# base_board7.net
KiCad netlist of a schematic drawn in EAGLE
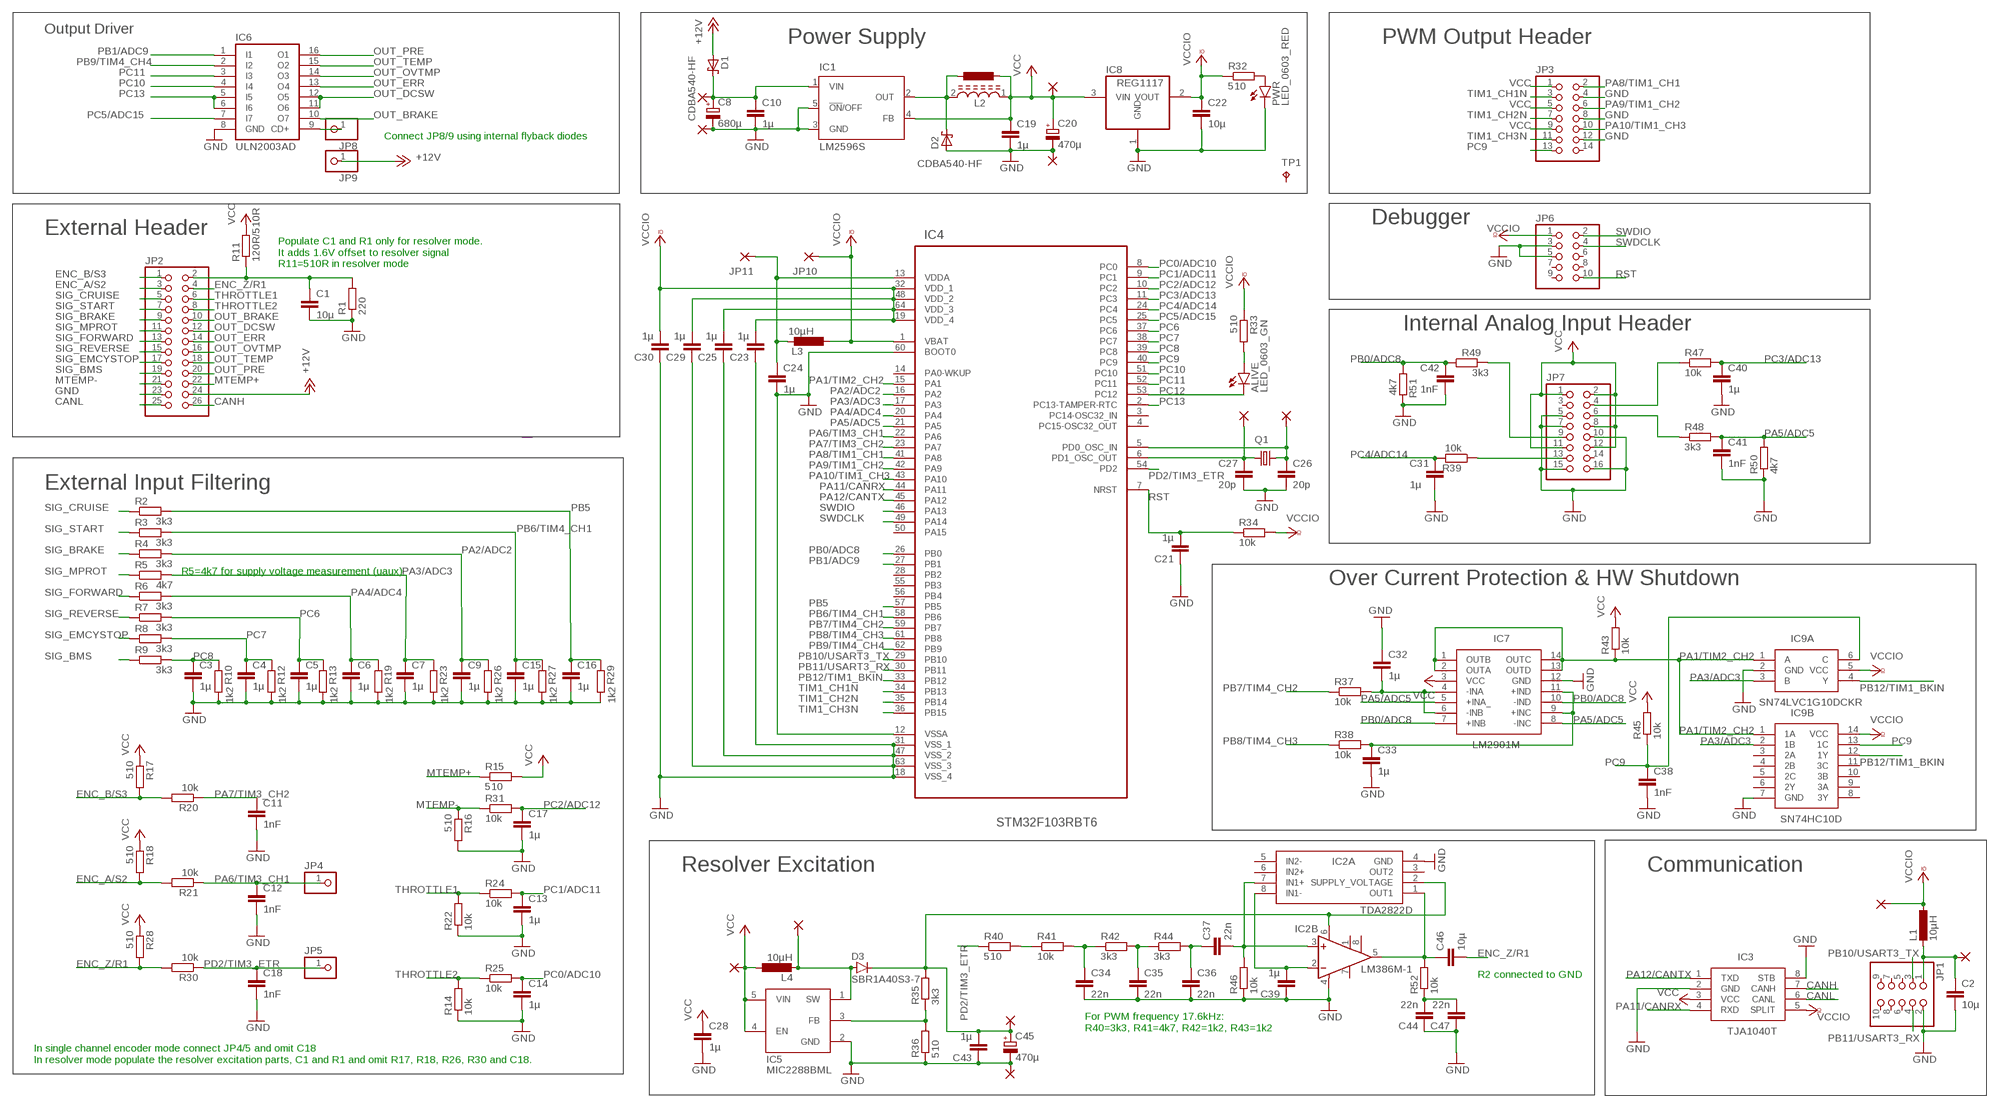
[diagram p0: schematic, sheet 1]

(export (version "E")
  (design (tool "Eeschema 10.0.6"))
  (components
    (comp (ref "ALIVE")
      (value "LED_0603_GN")
      (footprint "eagle-import:SML0805")
      (libsource (lib "eagle-import") (part "LEDSML0805"))
    )
    (comp (ref "C1")
      (value "10µ")
      (footprint "eagle-import:C0805K")
      (libsource (lib "eagle-import") (part "C-EUC0805K"))
    )
    (comp (ref "C2")
      (value "10µ")
      (footprint "eagle-import:C0805K")
      (libsource (lib "eagle-import") (part "C-EUC0805K"))
    )
    (comp (ref "C3")
      (value "1µ")
      (footprint "eagle-import:C0603K")
      (libsource (lib "eagle-import") (part "C-EUC0603K"))
    )
    (comp (ref "C4")
      (value "1µ")
      (footprint "eagle-import:C0603K")
      (libsource (lib "eagle-import") (part "C-EUC0603K"))
    )
    (comp (ref "C5")
      (value "1µ")
      (footprint "eagle-import:C0603K")
      (libsource (lib "eagle-import") (part "C-EUC0603K"))
    )
    (comp (ref "C6")
      (value "1µ")
      (footprint "eagle-import:C0603K")
      (libsource (lib "eagle-import") (part "C-EUC0603K"))
    )
    (comp (ref "C7")
      (value "1µ")
      (footprint "eagle-import:C0603K")
      (libsource (lib "eagle-import") (part "C-EUC0603K"))
    )
    (comp (ref "C8")
      (value "680µ")
      (footprint "eagle-import:153CLV-1014")
      (libsource (lib "eagle-import") (part "CPOL-EU153CLV-1014"))
    )
    (comp (ref "C9")
      (value "1µ")
      (footprint "eagle-import:C0603K")
      (libsource (lib "eagle-import") (part "C-EUC0603K"))
    )
    (comp (ref "C10")
      (value "1µ")
      (footprint "eagle-import:C0603K")
      (libsource (lib "eagle-import") (part "C-EUC0603K"))
    )
    (comp (ref "C11")
      (value "1nF")
      (footprint "eagle-import:C0603K")
      (libsource (lib "eagle-import") (part "C-EUC0603K"))
    )
    (comp (ref "C12")
      (value "1nF")
      (footprint "eagle-import:C0603K")
      (libsource (lib "eagle-import") (part "C-EUC0603K"))
    )
    (comp (ref "C13")
      (value "1µ")
      (footprint "eagle-import:C0603K")
      (libsource (lib "eagle-import") (part "C-EUC0603K"))
    )
    (comp (ref "C14")
      (value "1µ")
      (footprint "eagle-import:C0603K")
      (libsource (lib "eagle-import") (part "C-EUC0603K"))
    )
    (comp (ref "C15")
      (value "1µ")
      (footprint "eagle-import:C0603K")
      (libsource (lib "eagle-import") (part "C-EUC0603K"))
    )
    (comp (ref "C16")
      (value "1µ")
      (footprint "eagle-import:C0603K")
      (libsource (lib "eagle-import") (part "C-EUC0603K"))
    )
    (comp (ref "C17")
      (value "1µ")
      (footprint "eagle-import:C0603K")
      (libsource (lib "eagle-import") (part "C-EUC0603K"))
    )
    (comp (ref "C18")
      (value "1nF")
      (footprint "eagle-import:C0603K")
      (libsource (lib "eagle-import") (part "C-EUC0603K"))
    )
    (comp (ref "C19")
      (value "1µ")
      (footprint "eagle-import:C0603K")
      (libsource (lib "eagle-import") (part "C-EUC0603K"))
    )
    (comp (ref "C20")
      (value "470µ")
      (footprint "eagle-import:153CLV-0605")
      (libsource (lib "eagle-import") (part "CPOL-EU153CLV-0605"))
    )
    (comp (ref "C21")
      (value "1µ")
      (footprint "eagle-import:C0603K")
      (libsource (lib "eagle-import") (part "C-EUC0603K"))
    )
    (comp (ref "C22")
      (value "10µ")
      (footprint "eagle-import:C0805K")
      (libsource (lib "eagle-import") (part "C-EUC0805K"))
    )
    (comp (ref "C23")
      (value "1µ")
      (footprint "eagle-import:C0603K")
      (libsource (lib "eagle-import") (part "C-EUC0603K"))
    )
    (comp (ref "C24")
      (value "1µ")
      (footprint "eagle-import:C0603K")
      (libsource (lib "eagle-import") (part "C-EUC0603K"))
    )
    (comp (ref "C25")
      (value "1µ")
      (footprint "eagle-import:C0603K")
      (libsource (lib "eagle-import") (part "C-EUC0603K"))
    )
    (comp (ref "C26")
      (value "20p")
      (footprint "eagle-import:C0603K")
      (libsource (lib "eagle-import") (part "C-EUC0603K"))
    )
    (comp (ref "C27")
      (value "20p")
      (footprint "eagle-import:C0603K")
      (libsource (lib "eagle-import") (part "C-EUC0603K"))
    )
    (comp (ref "C28")
      (value "1µ")
      (footprint "eagle-import:C0603K")
      (libsource (lib "eagle-import") (part "C-EUC0603K"))
    )
    (comp (ref "C29")
      (value "1µ")
      (footprint "eagle-import:C0603K")
      (libsource (lib "eagle-import") (part "C-EUC0603K"))
    )
    (comp (ref "C30")
      (value "1µ")
      (footprint "eagle-import:C0603K")
      (libsource (lib "eagle-import") (part "C-EUC0603K"))
    )
    (comp (ref "C31")
      (value "1µ")
      (footprint "eagle-import:C0603K")
      (libsource (lib "eagle-import") (part "C-EUC0603K"))
    )
    (comp (ref "C32")
      (value "1µ")
      (footprint "eagle-import:C0603K")
      (libsource (lib "eagle-import") (part "C-EUC0603K"))
    )
    (comp (ref "C33")
      (value "1µ")
      (footprint "eagle-import:C0603K")
      (libsource (lib "eagle-import") (part "C-EUC0603K"))
    )
    (comp (ref "C34")
      (value "22n")
      (footprint "eagle-import:C0603K")
      (libsource (lib "eagle-import") (part "C-EUC0603K"))
    )
    (comp (ref "C35")
      (value "22n")
      (footprint "eagle-import:C0603K")
      (libsource (lib "eagle-import") (part "C-EUC0603K"))
    )
    (comp (ref "C36")
      (value "22n")
      (footprint "eagle-import:C0603K")
      (libsource (lib "eagle-import") (part "C-EUC0603K"))
    )
    (comp (ref "C37")
      (value "22n")
      (footprint "eagle-import:C0603K")
      (libsource (lib "eagle-import") (part "C-EUC0603K"))
    )
    (comp (ref "C38")
      (value "1nF")
      (footprint "eagle-import:C0603K")
      (libsource (lib "eagle-import") (part "C-EUC0603K"))
    )
    (comp (ref "C39")
      (value "1µ")
      (footprint "eagle-import:C0603K")
      (libsource (lib "eagle-import") (part "C-EUC0603K"))
    )
    (comp (ref "C40")
      (value "1µ")
      (footprint "eagle-import:C0603K")
      (libsource (lib "eagle-import") (part "C-EUC0603K"))
    )
    (comp (ref "C41")
      (value "1nF")
      (footprint "eagle-import:C0603K")
      (libsource (lib "eagle-import") (part "C-EUC0603K"))
    )
    (comp (ref "C42")
      (value "1nF")
      (footprint "eagle-import:C0603K")
      (libsource (lib "eagle-import") (part "C-EUC0603K"))
    )
    (comp (ref "C43")
      (value "1µ")
      (footprint "eagle-import:C0603K")
      (libsource (lib "eagle-import") (part "C-EUC0603K"))
    )
    (comp (ref "C44")
      (value "22n")
      (footprint "eagle-import:C0603K")
      (libsource (lib "eagle-import") (part "C-EUC0603K"))
    )
    (comp (ref "C45")
      (value "470µ")
      (footprint "eagle-import:153CLV-0605")
      (libsource (lib "eagle-import") (part "CPOL-EU153CLV-0605"))
    )
    (comp (ref "C46")
      (value "10µ")
      (footprint "eagle-import:C0805K")
      (libsource (lib "eagle-import") (part "C-EUC0805K"))
    )
    (comp (ref "C47")
      (value "22n")
      (footprint "eagle-import:C0603K")
      (libsource (lib "eagle-import") (part "C-EUC0603K"))
    )
    (comp (ref "D1")
      (value "CDBA540-HF")
      (footprint "eagle-import:SMB")
      (libsource (lib "eagle-import") (part "SCHOTTKY-DIODESMD"))
    )
    (comp (ref "D2")
      (value "CDBA540-HF")
      (footprint "eagle-import:SMB")
      (libsource (lib "eagle-import") (part "SCHOTTKY-DIODESMD"))
    )
    (comp (ref "D3")
      (value "SBR1A40S3-7")
      (footprint "eagle-import:SOD123")
      (libsource (lib "eagle-import") (part "D-SOD123"))
    )
    (comp (ref "IC1")
      (value "LM2596S")
      (footprint "eagle-import:TO263-5")
      (fields (field (name "MF") "NATIONAL SEMICONDUCTOR") (field (name "MPN") "LM2596S-ADJ/NOPB"))
      (libsource (lib "eagle-import") (part "LM2596S"))
    )
    (comp (ref "IC2A")
      (value "TDA2822D")
      (footprint "eagle-import:SOIC127P600X175-8N")
      (fields (field (name "MOUSER_PART_NUMBER") "511-TDA2822D") (field (name "RS_PART_NUMBER") "0426162P"))
      (libsource (lib "eagle-import") (part "TDA2822D"))
    )
    (comp (ref "IC2B")
      (value "LM386M-1")
      (footprint "eagle-import:SO08")
      (libsource (lib "eagle-import") (part "LM386?-M1"))
    )
    (comp (ref "IC3")
      (value "TJA1040T")
      (footprint "eagle-import:SOIC127P600X175-8N")
      (fields (field (name "MOUSER_PART_NUMBER") "4837547"))
      (libsource (lib "eagle-import") (part "TJA1040T"))
    )
    (comp (ref "IC4")
      (value "STM32F103RBT6")
      (footprint "eagle-import:QFP50P1200X1200X160-64N")
      (fields (field (name "DIGI-KEY_PART_NUMBER") "497-6066-ND") (field (name "MF") "STMicroelectronics"))
      (libsource (lib "eagle-import") (part "STM32F103RBT6"))
    )
    (comp (ref "IC5")
      (value "MIC2288BML")
      (footprint "eagle-import:SOT23-5L")
      (libsource (lib "eagle-import") (part "MIC2288BML"))
    )
    (comp (ref "IC6")
      (value "ULN2003AD")
      (footprint "eagle-import:SO16")
      (libsource (lib "eagle-import") (part "ULN2003AD"))
    )
    (comp (ref "IC7")
      (value "LM2901M")
      (footprint "eagle-import:SOP127P600X180-14N")
      (fields (field (name "MOUSER_PART_NUMBER") "4716204"))
      (libsource (lib "eagle-import") (part "LM2901M"))
    )
    (comp (ref "IC8")
      (value "REG1117")
      (footprint "eagle-import:SOT223")
      (libsource (lib "eagle-import") (part "REG1117"))
    )
    (comp (ref "IC9A")
      (value "SN74LVC1G10DCKR")
      (footprint "eagle-import:SOT65P210X110-6N")
      (fields
        (field (name "MOUSER_PART_NUMBER") "595-SN74LVC1G10DCKR")
        (field (name "RS_PART_NUMBER") "1627462")
      )
      (libsource (lib "eagle-import") (part "SN74LVC1G10DCKR"))
    )
    (comp (ref "IC9B")
      (value "SN74HC10D")
      (footprint "eagle-import:SOIC127P600X175-14N")
      (fields (field (name "MOUSER_PART_NUMBER") "595-SN74HC10D") (field (name "RS_PART_NUMBER") "6631896P"))
      (libsource (lib "eagle-import") (part "SN74HC10D"))
    )
    (comp (ref "JP1")
      (value "PINHD-2X5/90")
      (footprint "eagle-import:2X05_90")
      (libsource (lib "eagle-import") (part "PINHD-2X5/90"))
    )
    (comp (ref "JP2")
      (value "PINHD-2X13")
      (footprint "eagle-import:2X13")
      (libsource (lib "eagle-import") (part "PINHD-2X13"))
    )
    (comp (ref "JP3")
      (value "PINHD-2X7")
      (footprint "eagle-import:2X07")
      (libsource (lib "eagle-import") (part "PINHD-2X7"))
    )
    (comp (ref "JP4")
      (value "PINHD-1X1")
      (footprint "eagle-import:1X01")
      (libsource (lib "eagle-import") (part "PINHD-1X1"))
    )
    (comp (ref "JP5")
      (value "PINHD-1X1")
      (footprint "eagle-import:1X01")
      (libsource (lib "eagle-import") (part "PINHD-1X1"))
    )
    (comp (ref "JP6")
      (value "PINHD-2X5")
      (footprint "eagle-import:2X05")
      (libsource (lib "eagle-import") (part "PINHD-2X5"))
    )
    (comp (ref "JP7")
      (value "PINHD-2X8")
      (footprint "eagle-import:2X08")
      (libsource (lib "eagle-import") (part "PINHD-2X8"))
    )
    (comp (ref "JP8")
      (value "PINHD-1X1")
      (footprint "eagle-import:1X01")
      (libsource (lib "eagle-import") (part "PINHD-1X1"))
    )
    (comp (ref "JP9")
      (value "PINHD-1X1")
      (footprint "eagle-import:1X01")
      (libsource (lib "eagle-import") (part "PINHD-1X1"))
    )
    (comp (ref "JP10")
      (value "1,6/0,9")
      (footprint "eagle-import:1,6_0,9")
      (libsource (lib "eagle-import") (part "1,6/0,9"))
    )
    (comp (ref "JP11")
      (value "1,6/0,9")
      (footprint "eagle-import:1,6_0,9")
      (libsource (lib "eagle-import") (part "1,6/0,9"))
    )
    (comp (ref "JP12")
      (value "1,6/0,8")
      (footprint "eagle-import:1,6_0,8")
      (libsource (lib "eagle-import") (part "1,6/0,8"))
    )
    (comp (ref "JP13")
      (value "1,6/0,8")
      (footprint "eagle-import:1,6_0,8")
      (libsource (lib "eagle-import") (part "1,6/0,8"))
    )
    (comp (ref "JP14")
      (value "1,6/0,8")
      (footprint "eagle-import:1,6_0,8")
      (libsource (lib "eagle-import") (part "1,6/0,8"))
    )
    (comp (ref "JP15")
      (value "1,6/0,8")
      (footprint "eagle-import:1,6_0,8")
      (libsource (lib "eagle-import") (part "1,6/0,8"))
    )
    (comp (ref "JP16")
      (value "1,6/0,8")
      (footprint "eagle-import:1,6_0,8")
      (libsource (lib "eagle-import") (part "1,6/0,8"))
    )
    (comp (ref "JP17")
      (value "1,6/0,8")
      (footprint "eagle-import:1,6_0,8")
      (libsource (lib "eagle-import") (part "1,6/0,8"))
    )
    (comp (ref "L1")
      (value "10µH")
      (footprint "eagle-import:L3225M")
      (libsource (lib "eagle-import") (part "L-EUL3225M"))
    )
    (comp (ref "L2")
      (value "SRR1260-471K")
      (footprint "eagle-import:INDP125125X600N")
      (fields (field (name "MF") "Bourns"))
      (libsource (lib "eagle-import") (part "SRR1260-471K"))
    )
    (comp (ref "L3")
      (value "10µH")
      (footprint "eagle-import:L3225M")
      (libsource (lib "eagle-import") (part "L-EUL3225M"))
    )
    (comp (ref "L4")
      (value "10µH")
      (footprint "eagle-import:L3225M")
      (libsource (lib "eagle-import") (part "L-EUL3225M"))
    )
    (comp (ref "L5")
      (value "L-EUTJ3-U1")
      (footprint "eagle-import:TJ3-U1")
      (libsource (lib "eagle-import") (part "resistor_348_L-EUTJ3-U1"))
    )
    (comp (ref "PAD1")
      (value "1,6/0,9")
      (footprint "eagle-import:1,6_0,9")
      (libsource (lib "eagle-import") (part "1,6/0,9"))
    )
    (comp (ref "PAD2")
      (value "1,6/0,9")
      (footprint "eagle-import:1,6_0,9")
      (libsource (lib "eagle-import") (part "1,6/0,9"))
    )
    (comp (ref "PAD3")
      (value "1,6/0,8")
      (footprint "eagle-import:1,6_0,8")
      (libsource (lib "eagle-import") (part "1,6/0,8"))
    )
    (comp (ref "PAD4")
      (value "1,6/0,8")
      (footprint "eagle-import:1,6_0,8")
      (libsource (lib "eagle-import") (part "1,6/0,8"))
    )
    (comp (ref "PAD5")
      (value "1,6/0,8")
      (footprint "eagle-import:1,6_0,8")
      (libsource (lib "eagle-import") (part "1,6/0,8"))
    )
    (comp (ref "PAD6")
      (value "1,6/0,8")
      (footprint "eagle-import:1,6_0,8")
      (libsource (lib "eagle-import") (part "1,6/0,8"))
    )
    (comp (ref "PWR")
      (value "LED_0603_RED")
      (footprint "eagle-import:SML0805")
      (libsource (lib "eagle-import") (part "LEDSML0805"))
    )
    (comp (ref "Q1")
      (value "CSM-7X-DU")
      (footprint "eagle-import:CSM-7X-DU")
      (libsource (lib "eagle-import") (part "CSM-7X-DU"))
    )
    (comp (ref "R1")
      (value "220")
      (footprint "eagle-import:R0603")
      (libsource (lib "eagle-import") (part "R-EU_R0603"))
    )
    (comp (ref "R2")
      (value "3k3")
      (footprint "eagle-import:R0603")
      (libsource (lib "eagle-import") (part "R-EU_R0603"))
    )
    (comp (ref "R3")
      (value "3k3")
      (footprint "eagle-import:R0603")
      (libsource (lib "eagle-import") (part "R-EU_R0603"))
    )
    (comp (ref "R4")
      (value "3k3")
      (footprint "eagle-import:R0603")
      (libsource (lib "eagle-import") (part "R-EU_R0603"))
    )
    (comp (ref "R5")
      (value "4k7")
      (footprint "eagle-import:R0603")
      (libsource (lib "eagle-import") (part "R-EU_R0603"))
    )
    (comp (ref "R6")
      (value "3k3")
      (footprint "eagle-import:R0603")
      (libsource (lib "eagle-import") (part "R-EU_R0603"))
    )
    (comp (ref "R7")
      (value "3k3")
      (footprint "eagle-import:R0603")
      (libsource (lib "eagle-import") (part "R-EU_R0603"))
    )
    (comp (ref "R8")
      (value "3k3")
      (footprint "eagle-import:R0603")
      (libsource (lib "eagle-import") (part "R-EU_R0603"))
    )
    (comp (ref "R9")
      (value "3k3")
      (footprint "eagle-import:R0603")
      (libsource (lib "eagle-import") (part "R-EU_R0603"))
    )
    (comp (ref "R10")
      (value "1k2")
      (footprint "eagle-import:R0603")
      (libsource (lib "eagle-import") (part "R-EU_R0603"))
    )
    (comp (ref "R11")
      (value "120R/510R")
      (footprint "eagle-import:R0603")
      (libsource (lib "eagle-import") (part "R-EU_R0603"))
    )
    (comp (ref "R12")
      (value "1k2")
      (footprint "eagle-import:R0603")
      (libsource (lib "eagle-import") (part "R-EU_R0603"))
    )
    (comp (ref "R13")
      (value "1k2")
      (footprint "eagle-import:R0603")
      (libsource (lib "eagle-import") (part "R-EU_R0603"))
    )
    (comp (ref "R14")
      (value "10k")
      (footprint "eagle-import:R0603")
      (libsource (lib "eagle-import") (part "R-EU_R0603"))
    )
    (comp (ref "R15")
      (value "510")
      (footprint "eagle-import:R0603")
      (libsource (lib "eagle-import") (part "R-EU_R0603"))
    )
    (comp (ref "R16")
      (value "510")
      (footprint "eagle-import:R0603")
      (libsource (lib "eagle-import") (part "R-EU_R0603"))
    )
    (comp (ref "R17")
      (value "510")
      (footprint "eagle-import:R0603")
      (libsource (lib "eagle-import") (part "R-EU_R0603"))
    )
    (comp (ref "R18")
      (value "510")
      (footprint "eagle-import:R0603")
      (libsource (lib "eagle-import") (part "R-EU_R0603"))
    )
    (comp (ref "R19")
      (value "1k2")
      (footprint "eagle-import:R0603")
      (libsource (lib "eagle-import") (part "R-EU_R0603"))
    )
    (comp (ref "R20")
      (value "10k")
      (footprint "eagle-import:R0603")
      (libsource (lib "eagle-import") (part "R-EU_R0603"))
    )
    (comp (ref "R21")
      (value "10k")
      (footprint "eagle-import:R0603")
      (libsource (lib "eagle-import") (part "R-EU_R0603"))
    )
    (comp (ref "R22")
      (value "10k")
      (footprint "eagle-import:R0603")
      (libsource (lib "eagle-import") (part "R-EU_R0603"))
    )
    (comp (ref "R23")
      (value "1k2")
      (footprint "eagle-import:R0603")
      (libsource (lib "eagle-import") (part "R-EU_R0603"))
    )
    (comp (ref "R24")
      (value "10k")
      (footprint "eagle-import:R0603")
      (libsource (lib "eagle-import") (part "R-EU_R0603"))
    )
    (comp (ref "R25")
      (value "10k")
      (footprint "eagle-import:R0603")
      (libsource (lib "eagle-import") (part "R-EU_R0603"))
    )
    (comp (ref "R26")
      (value "1k2")
      (footprint "eagle-import:R0603")
      (libsource (lib "eagle-import") (part "R-EU_R0603"))
    )
    (comp (ref "R27")
      (value "1k2")
      (footprint "eagle-import:R0603")
      (libsource (lib "eagle-import") (part "R-EU_R0603"))
    )
    (comp (ref "R28")
      (value "510")
      (footprint "eagle-import:R0603")
      (libsource (lib "eagle-import") (part "R-EU_R0603"))
    )
    (comp (ref "R29")
      (value "1k2")
      (footprint "eagle-import:R0603")
      (libsource (lib "eagle-import") (part "R-EU_R0603"))
    )
    (comp (ref "R30")
      (value "10k")
      (footprint "eagle-import:R0603")
      (libsource (lib "eagle-import") (part "R-EU_R0603"))
    )
    (comp (ref "R31")
      (value "10k")
      (footprint "eagle-import:R0603")
      (libsource (lib "eagle-import") (part "R-EU_R0603"))
    )
    (comp (ref "R32")
      (value "510")
      (footprint "eagle-import:R0603")
      (libsource (lib "eagle-import") (part "R-EU_R0603"))
    )
    (comp (ref "R33")
      (value "510")
      (footprint "eagle-import:R0603")
      (libsource (lib "eagle-import") (part "R-EU_R0603"))
    )
    (comp (ref "R34")
      (value "10k")
      (footprint "eagle-import:R0603")
      (libsource (lib "eagle-import") (part "R-EU_R0603"))
    )
    (comp (ref "R35")
      (value "3k3")
      (footprint "eagle-import:R0603")
      (libsource (lib "eagle-import") (part "R-EU_R0603"))
    )
    (comp (ref "R36")
      (value "510")
      (footprint "eagle-import:R0603")
      (libsource (lib "eagle-import") (part "R-EU_R0603"))
    )
    (comp (ref "R37")
      (value "10k")
      (footprint "eagle-import:R0603")
      (libsource (lib "eagle-import") (part "R-EU_R0603"))
    )
    (comp (ref "R38")
      (value "10k")
      (footprint "eagle-import:R0603")
      (libsource (lib "eagle-import") (part "R-EU_R0603"))
    )
    (comp (ref "R39")
      (value "10k")
      (footprint "eagle-import:R0603")
      (libsource (lib "eagle-import") (part "R-EU_R0603"))
    )
    (comp (ref "R40")
      (value "510")
      (footprint "eagle-import:R0603")
      (libsource (lib "eagle-import") (part "R-EU_R0603"))
    )
    (comp (ref "R41")
      (value "10k")
      (footprint "eagle-import:R0603")
      (libsource (lib "eagle-import") (part "R-EU_R0603"))
    )
    (comp (ref "R42")
      (value "3k3")
      (footprint "eagle-import:R0603")
      (libsource (lib "eagle-import") (part "R-EU_R0603"))
    )
    (comp (ref "R43")
      (value "10k")
      (footprint "eagle-import:R0603")
      (libsource (lib "eagle-import") (part "R-EU_R0603"))
    )
    (comp (ref "R44")
      (value "3k3")
      (footprint "eagle-import:R0603")
      (libsource (lib "eagle-import") (part "R-EU_R0603"))
    )
    (comp (ref "R45")
      (value "10k")
      (footprint "eagle-import:R0603")
      (libsource (lib "eagle-import") (part "R-EU_R0603"))
    )
    (comp (ref "R46")
      (value "10k")
      (footprint "eagle-import:R0603")
      (libsource (lib "eagle-import") (part "R-EU_R0603"))
    )
    (comp (ref "R47")
      (value "10k")
      (footprint "eagle-import:R0603")
      (libsource (lib "eagle-import") (part "R-EU_R0603"))
    )
    (comp (ref "R48")
      (value "3k3")
      (footprint "eagle-import:R0603")
      (libsource (lib "eagle-import") (part "R-EU_R0603"))
    )
    (comp (ref "R49")
      (value "3k3")
      (footprint "eagle-import:R0603")
      (libsource (lib "eagle-import") (part "R-EU_R0603"))
    )
    (comp (ref "R50")
      (value "4k7")
      (footprint "eagle-import:R0603")
      (libsource (lib "eagle-import") (part "R-EU_R0603"))
    )
    (comp (ref "R51")
      (value "4k7")
      (footprint "eagle-import:R0603")
      (libsource (lib "eagle-import") (part "R-EU_R0603"))
    )
    (comp (ref "R52")
      (value "10k")
      (footprint "eagle-import:R0603")
      (libsource (lib "eagle-import") (part "R-EU_R0603"))
    )
    (comp (ref "TP1")
      (value "TPB1,27")
      (footprint "eagle-import:B1,27")
      (libsource (lib "eagle-import") (part "TPB1,27"))
    )
  )
  (nets
    (net (code "1") (name "+12V") (class "Default")
      (node (ref "D1") (pin "A") (pinfunction "A_A") (pintype "passive"))
      (node (ref "JP2") (pin "24") (pinfunction "24_24") (pintype "passive"))
      (node (ref "JP9") (pin "1") (pinfunction "1_1") (pintype "passive"))
    )
    (net (code "2") (name "/CANH") (class "Default")
      (node (ref "IC3") (pin "7") (pinfunction "CANH_7") (pintype "bidirectional"))
      (node (ref "JP2") (pin "26") (pinfunction "26_26") (pintype "passive"))
    )
    (net (code "3") (name "/CANL") (class "Default")
      (node (ref "IC3") (pin "6") (pinfunction "CANL_6") (pintype "bidirectional"))
      (node (ref "JP2") (pin "25") (pinfunction "25_25") (pintype "passive"))
    )
    (net (code "4") (name "/ENC_A{slash}S2") (class "Default")
      (node (ref "JP2") (pin "3") (pinfunction "3_3") (pintype "passive"))
      (node (ref "R18") (pin "2") (pinfunction "2_2") (pintype "passive"))
      (node (ref "R21") (pin "2") (pinfunction "2_2") (pintype "passive"))
    )
    (net (code "5") (name "/ENC_B{slash}S3") (class "Default")
      (node (ref "JP2") (pin "1") (pinfunction "1_1") (pintype "passive"))
      (node (ref "R17") (pin "2") (pinfunction "2_2") (pintype "passive"))
      (node (ref "R20") (pin "2") (pinfunction "2_2") (pintype "passive"))
    )
    (net (code "6") (name "/ENC_Z{slash}R1") (class "Default")
      (node (ref "C46") (pin "2") (pinfunction "2_2") (pintype "passive"))
      (node (ref "JP2") (pin "4") (pinfunction "4_4") (pintype "passive"))
      (node (ref "R28") (pin "2") (pinfunction "2_2") (pintype "passive"))
      (node (ref "R30") (pin "2") (pinfunction "2_2") (pintype "passive"))
    )
    (net (code "7") (name "/MTEMP+") (class "Default")
      (node (ref "JP2") (pin "22") (pinfunction "22_22") (pintype "passive"))
      (node (ref "R15") (pin "1") (pinfunction "1_1") (pintype "passive"))
    )
    (net (code "8") (name "/MTEMP-") (class "Default")
      (node (ref "JP2") (pin "21") (pinfunction "21_21") (pintype "passive"))
      (node (ref "R16") (pin "1") (pinfunction "1_1") (pintype "passive"))
      (node (ref "R31") (pin "1") (pinfunction "1_1") (pintype "passive"))
    )
    (net (code "9") (name "/OUT_BRAKE") (class "Default")
      (node (ref "IC6") (pin "10") (pinfunction "O7_10") (pintype "open_collector"))
      (node (ref "JP2") (pin "10") (pinfunction "10_10") (pintype "passive"))
    )
    (net (code "10") (name "/OUT_DCSW") (class "Default")
      (node (ref "IC6") (pin "11") (pinfunction "O6_11") (pintype "open_collector"))
      (node (ref "IC6") (pin "12") (pinfunction "O5_12") (pintype "open_collector"))
      (node (ref "JP2") (pin "12") (pinfunction "12_12") (pintype "passive"))
    )
    (net (code "11") (name "/OUT_ERR") (class "Default")
      (node (ref "IC6") (pin "13") (pinfunction "O4_13") (pintype "open_collector"))
      (node (ref "JP2") (pin "14") (pinfunction "14_14") (pintype "passive"))
    )
    (net (code "12") (name "/OUT_OVTMP") (class "Default")
      (node (ref "IC6") (pin "14") (pinfunction "O3_14") (pintype "open_collector"))
      (node (ref "JP2") (pin "16") (pinfunction "16_16") (pintype "passive"))
    )
    (net (code "13") (name "/OUT_PRE") (class "Default")
      (node (ref "IC6") (pin "16") (pinfunction "O1_16") (pintype "open_collector"))
      (node (ref "JP2") (pin "20") (pinfunction "20_20") (pintype "passive"))
    )
    (net (code "14") (name "/OUT_TEMP") (class "Default")
      (node (ref "IC6") (pin "15") (pinfunction "O2_15") (pintype "open_collector"))
      (node (ref "JP2") (pin "18") (pinfunction "18_18") (pintype "passive"))
    )
    (net (code "15") (name "/PA1{slash}TIM2_CH2") (class "Default")
      (node (ref "IC4") (pin "15") (pinfunction "PA1_15") (pintype "bidirectional"))
      (node (ref "IC7") (pin "1") (pinfunction "OUTB_1") (pintype "bidirectional"))
      (node (ref "IC7") (pin "13") (pinfunction "OUTD_13") (pintype "bidirectional"))
      (node (ref "IC7") (pin "14") (pinfunction "OUTC_14") (pintype "bidirectional"))
      (node (ref "IC7") (pin "2") (pinfunction "OUTA_2") (pintype "bidirectional"))
      (node (ref "IC9A") (pin "1") (pinfunction "A_1") (pintype "bidirectional"))
      (node (ref "IC9B") (pin "1") (pinfunction "1A_1") (pintype "bidirectional"))
      (node (ref "R43") (pin "1") (pinfunction "1_1") (pintype "passive"))
    )
    (net (code "16") (name "/PA2{slash}ADC2") (class "Default")
      (node (ref "C9") (pin "1") (pinfunction "1_1") (pintype "passive"))
      (node (ref "IC4") (pin "16") (pinfunction "PA2_16") (pintype "bidirectional"))
      (node (ref "R26") (pin "1") (pinfunction "1_1") (pintype "passive"))
      (node (ref "R4") (pin "2") (pinfunction "2_2") (pintype "passive"))
    )
    (net (code "17") (name "/PA3{slash}ADC3") (class "Default")
      (node (ref "C7") (pin "1") (pinfunction "1_1") (pintype "passive"))
      (node (ref "IC4") (pin "17") (pinfunction "PA3_17") (pintype "bidirectional"))
      (node (ref "IC9A") (pin "3") (pinfunction "B_3") (pintype "bidirectional"))
      (node (ref "IC9B") (pin "2") (pinfunction "1B_2") (pintype "bidirectional"))
      (node (ref "R23") (pin "1") (pinfunction "1_1") (pintype "passive"))
      (node (ref "R5") (pin "2") (pinfunction "2_2") (pintype "passive"))
    )
    (net (code "18") (name "/PA4{slash}ADC4") (class "Default")
      (node (ref "C6") (pin "1") (pinfunction "1_1") (pintype "passive"))
      (node (ref "IC4") (pin "20") (pinfunction "PA4_20") (pintype "bidirectional"))
      (node (ref "R19") (pin "1") (pinfunction "1_1") (pintype "passive"))
      (node (ref "R6") (pin "2") (pinfunction "2_2") (pintype "passive"))
    )
    (net (code "19") (name "/PA5{slash}ADC5") (class "Default")
      (node (ref "C41") (pin "1") (pinfunction "1_1") (pintype "passive"))
      (node (ref "IC4") (pin "21") (pinfunction "PA5_21") (pintype "bidirectional"))
      (node (ref "IC7") (pin "5") (pinfunction "+INA__5") (pintype "bidirectional"))
      (node (ref "IC7") (pin "8") (pinfunction "-INC_8") (pintype "bidirectional"))
      (node (ref "R48") (pin "2") (pinfunction "2_2") (pintype "passive"))
      (node (ref "R50") (pin "2") (pinfunction "2_2") (pintype "passive"))
    )
    (net (code "20") (name "/PA6{slash}TIM3_CH1") (class "Default")
      (node (ref "C12") (pin "1") (pinfunction "1_1") (pintype "passive"))
      (node (ref "IC4") (pin "22") (pinfunction "PA6_22") (pintype "bidirectional"))
      (node (ref "JP4") (pin "1") (pinfunction "1_1") (pintype "passive"))
      (node (ref "R21") (pin "1") (pinfunction "1_1") (pintype "passive"))
    )
    (net (code "21") (name "/PA7{slash}TIM3_CH2") (class "Default")
      (node (ref "C11") (pin "1") (pinfunction "1_1") (pintype "passive"))
      (node (ref "IC4") (pin "23") (pinfunction "PA7_23") (pintype "bidirectional"))
      (node (ref "R20") (pin "1") (pinfunction "1_1") (pintype "passive"))
    )
    (net (code "22") (name "/PA8{slash}TIM1_CH1") (class "Default")
      (node (ref "IC4") (pin "41") (pinfunction "PA8_41") (pintype "bidirectional"))
      (node (ref "JP3") (pin "2") (pinfunction "2_2") (pintype "passive"))
    )
    (net (code "23") (name "/PA9{slash}TIM1_CH2") (class "Default")
      (node (ref "IC4") (pin "42") (pinfunction "PA9_42") (pintype "bidirectional"))
      (node (ref "JP3") (pin "6") (pinfunction "6_6") (pintype "passive"))
    )
    (net (code "24") (name "/PA10{slash}TIM1_CH3") (class "Default")
      (node (ref "IC4") (pin "43") (pinfunction "PA10_43") (pintype "bidirectional"))
      (node (ref "JP3") (pin "10") (pinfunction "10_10") (pintype "passive"))
    )
    (net (code "25") (name "/PA11{slash}CANRX") (class "Default")
      (node (ref "IC3") (pin "4") (pinfunction "RXD_4") (pintype "output"))
      (node (ref "IC4") (pin "44") (pinfunction "PA11_44") (pintype "bidirectional"))
    )
    (net (code "26") (name "/PA12{slash}CANTX") (class "Default")
      (node (ref "IC3") (pin "1") (pinfunction "TXD_1") (pintype "input"))
      (node (ref "IC4") (pin "45") (pinfunction "PA12_45") (pintype "bidirectional"))
    )
    (net (code "27") (name "/PB0{slash}ADC8") (class "Default")
      (node (ref "C42") (pin "1") (pinfunction "1_1") (pintype "passive"))
      (node (ref "IC4") (pin "26") (pinfunction "PB0_26") (pintype "bidirectional"))
      (node (ref "IC7") (pin "10") (pinfunction "-IND_10") (pintype "bidirectional"))
      (node (ref "IC7") (pin "7") (pinfunction "+INB_7") (pintype "bidirectional"))
      (node (ref "R49") (pin "1") (pinfunction "1_1") (pintype "passive"))
      (node (ref "R51") (pin "1") (pinfunction "1_1") (pintype "passive"))
    )
    (net (code "28") (name "/PB1{slash}ADC9") (class "Default")
      (node (ref "IC4") (pin "27") (pinfunction "PB1_27") (pintype "bidirectional"))
      (node (ref "IC6") (pin "1") (pinfunction "I1_1") (pintype "input"))
    )
    (net (code "29") (name "/PB5") (class "Default")
      (node (ref "C16") (pin "1") (pinfunction "1_1") (pintype "passive"))
      (node (ref "IC4") (pin "57") (pinfunction "PB5_57") (pintype "bidirectional"))
      (node (ref "R2") (pin "2") (pinfunction "2_2") (pintype "passive"))
      (node (ref "R29") (pin "1") (pinfunction "1_1") (pintype "passive"))
    )
    (net (code "30") (name "/PB6{slash}TIM4_CH1") (class "Default")
      (node (ref "C15") (pin "1") (pinfunction "1_1") (pintype "passive"))
      (node (ref "IC4") (pin "58") (pinfunction "PB6_58") (pintype "bidirectional"))
      (node (ref "R27") (pin "1") (pinfunction "1_1") (pintype "passive"))
      (node (ref "R3") (pin "2") (pinfunction "2_2") (pintype "passive"))
    )
    (net (code "31") (name "/PB7{slash}TIM4_CH2") (class "Default")
      (node (ref "IC4") (pin "59") (pinfunction "PB7_59") (pintype "bidirectional"))
      (node (ref "R37") (pin "1") (pinfunction "1_1") (pintype "passive"))
    )
    (net (code "32") (name "/PB8{slash}TIM4_CH3") (class "Default")
      (node (ref "IC4") (pin "61") (pinfunction "PB8_61") (pintype "bidirectional"))
      (node (ref "R38") (pin "1") (pinfunction "1_1") (pintype "passive"))
    )
    (net (code "33") (name "/PB9{slash}TIM4_CH4") (class "Default")
      (node (ref "IC4") (pin "62") (pinfunction "PB9_62") (pintype "bidirectional"))
      (node (ref "IC6") (pin "2") (pinfunction "I2_2") (pintype "input"))
    )
    (net (code "34") (name "/PB10{slash}USART3_TX") (class "Default")
      (node (ref "IC4") (pin "29") (pinfunction "PB10_29") (pintype "bidirectional"))
      (node (ref "JP1") (pin "3") (pinfunction "3_3") (pintype "passive"))
    )
    (net (code "35") (name "/PB11{slash}USART3_RX") (class "Default")
      (node (ref "IC4") (pin "30") (pinfunction "PB11_30") (pintype "bidirectional"))
      (node (ref "JP1") (pin "4") (pinfunction "4_4") (pintype "passive"))
    )
    (net (code "36") (name "/PB12{slash}TIM1_BKIN") (class "Default")
      (node (ref "IC4") (pin "33") (pinfunction "PB12_33") (pintype "bidirectional"))
      (node (ref "IC9A") (pin "4") (pinfunction "Y_4") (pintype "bidirectional"))
      (node (ref "IC9B") (pin "12") (pinfunction "1Y_12") (pintype "bidirectional"))
    )
    (net (code "37") (name "/PC0{slash}ADC10") (class "Default")
      (node (ref "C14") (pin "1") (pinfunction "1_1") (pintype "passive"))
      (node (ref "IC4") (pin "8") (pinfunction "PC0_8") (pintype "bidirectional"))
      (node (ref "R25") (pin "2") (pinfunction "2_2") (pintype "passive"))
    )
    (net (code "38") (name "/PC1{slash}ADC11") (class "Default")
      (node (ref "C13") (pin "1") (pinfunction "1_1") (pintype "passive"))
      (node (ref "IC4") (pin "9") (pinfunction "PC1_9") (pintype "bidirectional"))
      (node (ref "R24") (pin "2") (pinfunction "2_2") (pintype "passive"))
    )
    (net (code "39") (name "/PC2{slash}ADC12") (class "Default")
      (node (ref "C17") (pin "1") (pinfunction "1_1") (pintype "passive"))
      (node (ref "IC4") (pin "10") (pinfunction "PC2_10") (pintype "bidirectional"))
      (node (ref "R31") (pin "2") (pinfunction "2_2") (pintype "passive"))
    )
    (net (code "40") (name "/PC3{slash}ADC13") (class "Default")
      (node (ref "C40") (pin "1") (pinfunction "1_1") (pintype "passive"))
      (node (ref "IC4") (pin "11") (pinfunction "PC3_11") (pintype "bidirectional"))
      (node (ref "R47") (pin "2") (pinfunction "2_2") (pintype "passive"))
    )
    (net (code "41") (name "/PC4{slash}ADC14") (class "Default")
      (node (ref "C31") (pin "1") (pinfunction "1_1") (pintype "passive"))
      (node (ref "IC4") (pin "24") (pinfunction "PC4_24") (pintype "bidirectional"))
      (node (ref "R39") (pin "2") (pinfunction "2_2") (pintype "passive"))
    )
    (net (code "42") (name "/PC5{slash}ADC15") (class "Default")
      (node (ref "IC4") (pin "25") (pinfunction "PC5_25") (pintype "bidirectional"))
      (node (ref "IC6") (pin "7") (pinfunction "I7_7") (pintype "input"))
    )
    (net (code "43") (name "/PC6") (class "Default")
      (node (ref "C5") (pin "1") (pinfunction "1_1") (pintype "passive"))
      (node (ref "IC4") (pin "37") (pinfunction "PC6_37") (pintype "bidirectional"))
      (node (ref "R13") (pin "1") (pinfunction "1_1") (pintype "passive"))
      (node (ref "R7") (pin "2") (pinfunction "2_2") (pintype "passive"))
    )
    (net (code "44") (name "/PC7") (class "Default")
      (node (ref "C4") (pin "1") (pinfunction "1_1") (pintype "passive"))
      (node (ref "IC4") (pin "38") (pinfunction "PC7_38") (pintype "bidirectional"))
      (node (ref "R12") (pin "1") (pinfunction "1_1") (pintype "passive"))
      (node (ref "R8") (pin "2") (pinfunction "2_2") (pintype "passive"))
    )
    (net (code "45") (name "/PC8") (class "Default")
      (node (ref "C3") (pin "1") (pinfunction "1_1") (pintype "passive"))
      (node (ref "IC4") (pin "39") (pinfunction "PC8_39") (pintype "bidirectional"))
      (node (ref "R10") (pin "1") (pinfunction "1_1") (pintype "passive"))
      (node (ref "R9") (pin "2") (pinfunction "2_2") (pintype "passive"))
    )
    (net (code "46") (name "/PC9") (class "Default")
      (node (ref "C38") (pin "1") (pinfunction "1_1") (pintype "passive"))
      (node (ref "IC4") (pin "40") (pinfunction "PC9_40") (pintype "bidirectional"))
      (node (ref "IC9A") (pin "6") (pinfunction "C_6") (pintype "bidirectional"))
      (node (ref "IC9B") (pin "13") (pinfunction "1C_13") (pintype "bidirectional"))
      (node (ref "JP3") (pin "13") (pinfunction "13_13") (pintype "passive"))
      (node (ref "R45") (pin "1") (pinfunction "1_1") (pintype "passive"))
    )
    (net (code "47") (name "/PC10") (class "Default")
      (node (ref "IC4") (pin "51") (pinfunction "PC10_51") (pintype "bidirectional"))
      (node (ref "IC6") (pin "4") (pinfunction "I4_4") (pintype "input"))
    )
    (net (code "48") (name "/PC11") (class "Default")
      (node (ref "IC4") (pin "52") (pinfunction "PC11_52") (pintype "bidirectional"))
      (node (ref "IC6") (pin "3") (pinfunction "I3_3") (pintype "input"))
    )
    (net (code "49") (name "/PC12") (class "Default")
      (node (ref "ALIVE") (pin "C") (pinfunction "C_C") (pintype "passive"))
      (node (ref "IC4") (pin "53") (pinfunction "PC12_53") (pintype "bidirectional"))
    )
    (net (code "50") (name "/PC13") (class "Default")
      (node (ref "IC4") (pin "2") (pinfunction "PC13-TAMPER-RTC_2") (pintype "bidirectional"))
      (node (ref "IC6") (pin "5") (pinfunction "I5_5") (pintype "input"))
      (node (ref "IC6") (pin "6") (pinfunction "I6_6") (pintype "input"))
    )
    (net (code "51") (name "/PD2{slash}TIM3_ETR") (class "Default")
      (node (ref "C18") (pin "1") (pinfunction "1_1") (pintype "passive"))
      (node (ref "IC4") (pin "54") (pinfunction "PD2_54") (pintype "bidirectional"))
      (node (ref "JP5") (pin "1") (pinfunction "1_1") (pintype "passive"))
      (node (ref "R30") (pin "1") (pinfunction "1_1") (pintype "passive"))
      (node (ref "R40") (pin "1") (pinfunction "1_1") (pintype "passive"))
    )
    (net (code "52") (name "/RST") (class "Default")
      (node (ref "C21") (pin "2") (pinfunction "2_2") (pintype "passive"))
      (node (ref "IC4") (pin "7") (pinfunction "NRST_7") (pintype "bidirectional"))
      (node (ref "JP6") (pin "10") (pinfunction "10_10") (pintype "passive"))
      (node (ref "R34") (pin "1") (pinfunction "1_1") (pintype "passive"))
    )
    (net (code "53") (name "/SIG_BMS") (class "Default")
      (node (ref "JP2") (pin "19") (pinfunction "19_19") (pintype "passive"))
      (node (ref "R9") (pin "1") (pinfunction "1_1") (pintype "passive"))
    )
    (net (code "54") (name "/SIG_BRAKE") (class "Default")
      (node (ref "JP2") (pin "9") (pinfunction "9_9") (pintype "passive"))
      (node (ref "R4") (pin "1") (pinfunction "1_1") (pintype "passive"))
    )
    (net (code "55") (name "/SIG_CRUISE") (class "Default")
      (node (ref "JP2") (pin "5") (pinfunction "5_5") (pintype "passive"))
      (node (ref "R2") (pin "1") (pinfunction "1_1") (pintype "passive"))
    )
    (net (code "56") (name "/SIG_EMCYSTOP") (class "Default")
      (node (ref "JP2") (pin "17") (pinfunction "17_17") (pintype "passive"))
      (node (ref "R8") (pin "1") (pinfunction "1_1") (pintype "passive"))
    )
    (net (code "57") (name "/SIG_FORWARD") (class "Default")
      (node (ref "JP2") (pin "13") (pinfunction "13_13") (pintype "passive"))
      (node (ref "R6") (pin "1") (pinfunction "1_1") (pintype "passive"))
    )
    (net (code "58") (name "/SIG_MPROT") (class "Default")
      (node (ref "JP2") (pin "11") (pinfunction "11_11") (pintype "passive"))
      (node (ref "R5") (pin "1") (pinfunction "1_1") (pintype "passive"))
    )
    (net (code "59") (name "/SIG_REVERSE") (class "Default")
      (node (ref "JP2") (pin "15") (pinfunction "15_15") (pintype "passive"))
      (node (ref "R7") (pin "1") (pinfunction "1_1") (pintype "passive"))
    )
    (net (code "60") (name "/SIG_START") (class "Default")
      (node (ref "JP2") (pin "7") (pinfunction "7_7") (pintype "passive"))
      (node (ref "R3") (pin "1") (pinfunction "1_1") (pintype "passive"))
    )
    (net (code "61") (name "/SWDCLK") (class "Default")
      (node (ref "IC4") (pin "49") (pinfunction "PA14_49") (pintype "bidirectional"))
      (node (ref "JP6") (pin "4") (pinfunction "4_4") (pintype "passive"))
    )
    (net (code "62") (name "/SWDIO") (class "Default")
      (node (ref "IC4") (pin "46") (pinfunction "PA13_46") (pintype "bidirectional"))
      (node (ref "JP6") (pin "2") (pinfunction "2_2") (pintype "passive"))
    )
    (net (code "63") (name "/THROTTLE1") (class "Default")
      (node (ref "JP2") (pin "6") (pinfunction "6_6") (pintype "passive"))
      (node (ref "R22") (pin "2") (pinfunction "2_2") (pintype "passive"))
      (node (ref "R24") (pin "1") (pinfunction "1_1") (pintype "passive"))
    )
    (net (code "64") (name "/THROTTLE2") (class "Default")
      (node (ref "JP2") (pin "8") (pinfunction "8_8") (pintype "passive"))
      (node (ref "R14") (pin "2") (pinfunction "2_2") (pintype "passive"))
      (node (ref "R25") (pin "1") (pinfunction "1_1") (pintype "passive"))
    )
    (net (code "65") (name "/TIM1_CH1N") (class "Default")
      (node (ref "IC4") (pin "34") (pinfunction "PB13_34") (pintype "bidirectional"))
      (node (ref "JP3") (pin "3") (pinfunction "3_3") (pintype "passive"))
    )
    (net (code "66") (name "/TIM1_CH2N") (class "Default")
      (node (ref "IC4") (pin "35") (pinfunction "PB14_35") (pintype "bidirectional"))
      (node (ref "JP3") (pin "7") (pinfunction "7_7") (pintype "passive"))
    )
    (net (code "67") (name "/TIM1_CH3N") (class "Default")
      (node (ref "IC4") (pin "36") (pinfunction "PB15_36") (pintype "bidirectional"))
      (node (ref "JP3") (pin "11") (pinfunction "11_11") (pintype "passive"))
    )
    (net (code "68") (name "GND") (class "Default")
      (node (ref "C1") (pin "2") (pinfunction "2_2") (pintype "passive"))
      (node (ref "C10") (pin "2") (pinfunction "2_2") (pintype "passive"))
      (node (ref "C11") (pin "2") (pinfunction "2_2") (pintype "passive"))
      (node (ref "C12") (pin "2") (pinfunction "2_2") (pintype "passive"))
      (node (ref "C13") (pin "2") (pinfunction "2_2") (pintype "passive"))
      (node (ref "C14") (pin "2") (pinfunction "2_2") (pintype "passive"))
      (node (ref "C15") (pin "2") (pinfunction "2_2") (pintype "passive"))
      (node (ref "C16") (pin "2") (pinfunction "2_2") (pintype "passive"))
      (node (ref "C17") (pin "2") (pinfunction "2_2") (pintype "passive"))
      (node (ref "C18") (pin "2") (pinfunction "2_2") (pintype "passive"))
      (node (ref "C19") (pin "2") (pinfunction "2_2") (pintype "passive"))
      (node (ref "C2") (pin "2") (pinfunction "2_2") (pintype "passive"))
      (node (ref "C20") (pin "-") (pinfunction "-_-") (pintype "passive"))
      (node (ref "C21") (pin "1") (pinfunction "1_1") (pintype "passive"))
      (node (ref "C22") (pin "2") (pinfunction "2_2") (pintype "passive"))
      (node (ref "C23") (pin "1") (pinfunction "1_1") (pintype "passive"))
      (node (ref "C24") (pin "2") (pinfunction "2_2") (pintype "passive"))
      (node (ref "C25") (pin "1") (pinfunction "1_1") (pintype "passive"))
      (node (ref "C26") (pin "2") (pinfunction "2_2") (pintype "passive"))
      (node (ref "C27") (pin "2") (pinfunction "2_2") (pintype "passive"))
      (node (ref "C28") (pin "2") (pinfunction "2_2") (pintype "passive"))
      (node (ref "C29") (pin "1") (pinfunction "1_1") (pintype "passive"))
      (node (ref "C3") (pin "2") (pinfunction "2_2") (pintype "passive"))
      (node (ref "C30") (pin "1") (pinfunction "1_1") (pintype "passive"))
      (node (ref "C31") (pin "2") (pinfunction "2_2") (pintype "passive"))
      (node (ref "C32") (pin "1") (pinfunction "1_1") (pintype "passive"))
      (node (ref "C33") (pin "2") (pinfunction "2_2") (pintype "passive"))
      (node (ref "C34") (pin "2") (pinfunction "2_2") (pintype "passive"))
      (node (ref "C35") (pin "2") (pinfunction "2_2") (pintype "passive"))
      (node (ref "C36") (pin "2") (pinfunction "2_2") (pintype "passive"))
      (node (ref "C38") (pin "2") (pinfunction "2_2") (pintype "passive"))
      (node (ref "C39") (pin "1") (pinfunction "1_1") (pintype "passive"))
      (node (ref "C4") (pin "2") (pinfunction "2_2") (pintype "passive"))
      (node (ref "C40") (pin "2") (pinfunction "2_2") (pintype "passive"))
      (node (ref "C41") (pin "2") (pinfunction "2_2") (pintype "passive"))
      (node (ref "C42") (pin "2") (pinfunction "2_2") (pintype "passive"))
      (node (ref "C43") (pin "1") (pinfunction "1_1") (pintype "passive"))
      (node (ref "C44") (pin "1") (pinfunction "1_1") (pintype "passive"))
      (node (ref "C45") (pin "-") (pinfunction "-_-") (pintype "passive"))
      (node (ref "C47") (pin "1") (pinfunction "1_1") (pintype "passive"))
      (node (ref "C5") (pin "2") (pinfunction "2_2") (pintype "passive"))
      (node (ref "C6") (pin "2") (pinfunction "2_2") (pintype "passive"))
      (node (ref "C7") (pin "2") (pinfunction "2_2") (pintype "passive"))
      (node (ref "C8") (pin "-") (pinfunction "-_-") (pintype "passive"))
      (node (ref "C9") (pin "2") (pinfunction "2_2") (pintype "passive"))
      (node (ref "D2") (pin "A") (pinfunction "A_A") (pintype "passive"))
      (node (ref "IC1") (pin "3") (pinfunction "GND_3") (pintype "power_in"))
      (node (ref "IC1") (pin "5") (pinfunction "~{ON}/OFF_5") (pintype "input"))
      (node (ref "IC2A") (pin "4") (pinfunction "GND_4") (pintype "power_in"))
      (node (ref "IC2B") (pin "4") (pinfunction "GND_4") (pintype "power_in"))
      (node (ref "IC3") (pin "2") (pinfunction "GND_2") (pintype "power_in"))
      (node (ref "IC3") (pin "8") (pinfunction "STB_8") (pintype "input"))
      (node (ref "IC4") (pin "12") (pinfunction "VSSA_12") (pintype "passive"))
      (node (ref "IC4") (pin "18") (pinfunction "VSS_4_18") (pintype "passive"))
      (node (ref "IC4") (pin "31") (pinfunction "VSS_1_31") (pintype "passive"))
      (node (ref "IC4") (pin "47") (pinfunction "VSS_2_47") (pintype "passive"))
      (node (ref "IC4") (pin "60") (pinfunction "BOOT0_60") (pintype "input"))
      (node (ref "IC4") (pin "63") (pinfunction "VSS_3_63") (pintype "passive"))
      (node (ref "IC5") (pin "2") (pinfunction "GND_2") (pintype "bidirectional"))
      (node (ref "IC6") (pin "8") (pinfunction "GND_8") (pintype "power_in"))
      (node (ref "IC7") (pin "12") (pinfunction "GND_12") (pintype "bidirectional"))
      (node (ref "IC8") (pin "1") (pinfunction "GND_1") (pintype "power_in"))
      (node (ref "IC9A") (pin "2") (pinfunction "GND_2") (pintype "bidirectional"))
      (node (ref "IC9B") (pin "7") (pinfunction "GND_7") (pintype "power_in"))
      (node (ref "JP1") (pin "2") (pinfunction "2_2") (pintype "passive"))
      (node (ref "JP2") (pin "23") (pinfunction "23_23") (pintype "passive"))
      (node (ref "JP3") (pin "12") (pinfunction "12_12") (pintype "passive"))
      (node (ref "JP3") (pin "4") (pinfunction "4_4") (pintype "passive"))
      (node (ref "JP3") (pin "8") (pinfunction "8_8") (pintype "passive"))
      (node (ref "JP6") (pin "3") (pinfunction "3_3") (pintype "passive"))
      (node (ref "JP6") (pin "5") (pinfunction "5_5") (pintype "passive"))
      (node (ref "JP7") (pin "10") (pinfunction "10_10") (pintype "passive"))
      (node (ref "JP7") (pin "15") (pinfunction "15_15") (pintype "passive"))
      (node (ref "JP7") (pin "16") (pinfunction "16_16") (pintype "passive"))
      (node (ref "JP7") (pin "5") (pinfunction "5_5") (pintype "passive"))
      (node (ref "JP7") (pin "7") (pinfunction "7_7") (pintype "passive"))
      (node (ref "PAD1") (pin "1") (pinfunction "P_1") (pintype "passive"))
      (node (ref "PAD3") (pin "1") (pinfunction "P_1") (pintype "passive"))
      (node (ref "PAD6") (pin "1") (pinfunction "P_1") (pintype "passive"))
      (node (ref "PWR") (pin "C") (pinfunction "C_C") (pintype "passive"))
      (node (ref "R1") (pin "1") (pinfunction "1_1") (pintype "passive"))
      (node (ref "R10") (pin "2") (pinfunction "2_2") (pintype "passive"))
      (node (ref "R12") (pin "2") (pinfunction "2_2") (pintype "passive"))
      (node (ref "R13") (pin "2") (pinfunction "2_2") (pintype "passive"))
      (node (ref "R14") (pin "1") (pinfunction "1_1") (pintype "passive"))
      (node (ref "R16") (pin "2") (pinfunction "2_2") (pintype "passive"))
      (node (ref "R19") (pin "2") (pinfunction "2_2") (pintype "passive"))
      (node (ref "R22") (pin "1") (pinfunction "1_1") (pintype "passive"))
      (node (ref "R23") (pin "2") (pinfunction "2_2") (pintype "passive"))
      (node (ref "R26") (pin "2") (pinfunction "2_2") (pintype "passive"))
      (node (ref "R27") (pin "2") (pinfunction "2_2") (pintype "passive"))
      (node (ref "R29") (pin "2") (pinfunction "2_2") (pintype "passive"))
      (node (ref "R36") (pin "1") (pinfunction "1_1") (pintype "passive"))
      (node (ref "R46") (pin "1") (pinfunction "1_1") (pintype "passive"))
      (node (ref "R50") (pin "1") (pinfunction "1_1") (pintype "passive"))
      (node (ref "R51") (pin "2") (pinfunction "2_2") (pintype "passive"))
    )
    (net (code "69") (name "Net-(ALIVE-PadA)") (class "Default")
      (node (ref "ALIVE") (pin "A") (pinfunction "A_A") (pintype "passive"))
      (node (ref "R33") (pin "2") (pinfunction "2_2") (pintype "passive"))
    )
    (net (code "70") (name "Net-(C1-Pad1)") (class "Default")
      (node (ref "C1") (pin "1") (pinfunction "1_1") (pintype "passive"))
      (node (ref "JP2") (pin "2") (pinfunction "2_2") (pintype "passive"))
      (node (ref "R1") (pin "2") (pinfunction "2_2") (pintype "passive"))
      (node (ref "R11") (pin "1") (pinfunction "1_1") (pintype "passive"))
    )
    (net (code "71") (name "Net-(C34-Pad1)") (class "Default")
      (node (ref "C34") (pin "1") (pinfunction "1_1") (pintype "passive"))
      (node (ref "R41") (pin "2") (pinfunction "2_2") (pintype "passive"))
      (node (ref "R42") (pin "1") (pinfunction "1_1") (pintype "passive"))
    )
    (net (code "72") (name "Net-(C35-Pad1)") (class "Default")
      (node (ref "C35") (pin "1") (pinfunction "1_1") (pintype "passive"))
      (node (ref "R42") (pin "2") (pinfunction "2_2") (pintype "passive"))
      (node (ref "R44") (pin "1") (pinfunction "1_1") (pintype "passive"))
    )
    (net (code "73") (name "Net-(C36-Pad1)") (class "Default")
      (node (ref "C36") (pin "1") (pinfunction "1_1") (pintype "passive"))
      (node (ref "C37") (pin "1") (pinfunction "1_1") (pintype "passive"))
      (node (ref "R44") (pin "2") (pinfunction "2_2") (pintype "passive"))
    )
    (net (code "74") (name "Net-(C44-Pad2)") (class "Default")
      (node (ref "C44") (pin "2") (pinfunction "2_2") (pintype "passive"))
      (node (ref "C47") (pin "2") (pinfunction "2_2") (pintype "passive"))
      (node (ref "R52") (pin "1") (pinfunction "1_1") (pintype "passive"))
    )
    (net (code "75") (name "Net-(D3-A)") (class "Default")
      (node (ref "D3") (pin "2") (pinfunction "A_2") (pintype "passive"))
      (node (ref "IC5") (pin "1") (pinfunction "SW_1") (pintype "bidirectional"))
      (node (ref "JP13") (pin "1") (pinfunction "P_1") (pintype "passive"))
      (node (ref "L4") (pin "2") (pinfunction "2_2") (pintype "passive"))
    )
    (net (code "76") (name "Net-(D3-C)") (class "Default")
      (node (ref "C43") (pin "2") (pinfunction "2_2") (pintype "passive"))
      (node (ref "C45") (pin "+") (pinfunction "+_+") (pintype "passive"))
      (node (ref "D3") (pin "1") (pinfunction "C_1") (pintype "passive"))
      (node (ref "IC2A") (pin "2") (pinfunction "SUPPLY_VOLTAGE_2") (pintype "bidirectional"))
      (node (ref "IC2B") (pin "6") (pinfunction "VS_6") (pintype "power_in"))
      (node (ref "PAD5") (pin "1") (pinfunction "P_1") (pintype "passive"))
      (node (ref "R35") (pin "2") (pinfunction "2_2") (pintype "passive"))
    )
    (net (code "77") (name "Net-(IC1-OUT)") (class "Default")
      (node (ref "D2") (pin "C") (pinfunction "C_C") (pintype "passive"))
      (node (ref "IC1") (pin "2") (pinfunction "OUT_2") (pintype "output"))
      (node (ref "L2") (pin "2") (pinfunction "2_2") (pintype "passive"))
      (node (ref "L5") (pin "1") (pinfunction "1_1") (pintype "passive"))
    )
    (net (code "78") (name "Net-(IC1-VIN)") (class "Default")
      (node (ref "C10") (pin "1") (pinfunction "1_1") (pintype "passive"))
      (node (ref "C8") (pin "+") (pinfunction "+_+") (pintype "passive"))
      (node (ref "D1") (pin "C") (pinfunction "C_C") (pintype "passive"))
      (node (ref "IC1") (pin "1") (pinfunction "VIN_1") (pintype "input"))
      (node (ref "PAD2") (pin "1") (pinfunction "P_1") (pintype "passive"))
    )
    (net (code "79") (name "Net-(IC2A-IN1+)") (class "Default")
      (node (ref "C37") (pin "2") (pinfunction "2_2") (pintype "passive"))
      (node (ref "IC2A") (pin "7") (pinfunction "IN1+_7") (pintype "input"))
      (node (ref "IC2B") (pin "3") (pinfunction "+IN_3") (pintype "input"))
      (node (ref "R46") (pin "2") (pinfunction "2_2") (pintype "passive"))
    )
    (net (code "80") (name "Net-(IC2A-IN1-)") (class "Default")
      (node (ref "C39") (pin "2") (pinfunction "2_2") (pintype "passive"))
      (node (ref "IC2A") (pin "8") (pinfunction "IN1-_8") (pintype "input"))
      (node (ref "IC2B") (pin "2") (pinfunction "-IN_2") (pintype "input"))
    )
    (net (code "81") (name "Net-(IC2A-OUT1)") (class "Default")
      (node (ref "C46") (pin "1") (pinfunction "1_1") (pintype "passive"))
      (node (ref "IC2A") (pin "1") (pinfunction "OUT1_1") (pintype "output"))
      (node (ref "IC2B") (pin "5") (pinfunction "OUT_5") (pintype "output"))
      (node (ref "R52") (pin "2") (pinfunction "2_2") (pintype "passive"))
    )
    (net (code "82") (name "Net-(IC4-PD0_OSC_IN)") (class "Default")
      (node (ref "C26") (pin "1") (pinfunction "1_1") (pintype "passive"))
      (node (ref "IC4") (pin "5") (pinfunction "PD0_OSC_IN_5") (pintype "bidirectional"))
      (node (ref "JP16") (pin "1") (pinfunction "P_1") (pintype "passive"))
      (node (ref "Q1") (pin "2") (pinfunction "2_2") (pintype "passive"))
    )
    (net (code "83") (name "Net-(IC4-PD1_OSC_OUT)") (class "Default")
      (node (ref "C27") (pin "1") (pinfunction "1_1") (pintype "passive"))
      (node (ref "IC4") (pin "6") (pinfunction "PD1_OSC_OUT_6") (pintype "bidirectional"))
      (node (ref "JP17") (pin "1") (pinfunction "P_1") (pintype "passive"))
      (node (ref "Q1") (pin "1") (pinfunction "1_1") (pintype "passive"))
    )
    (net (code "84") (name "Net-(IC4-VDDA)") (class "Default")
      (node (ref "C24") (pin "1") (pinfunction "1_1") (pintype "passive"))
      (node (ref "IC4") (pin "13") (pinfunction "VDDA_13") (pintype "power_in"))
      (node (ref "JP11") (pin "1") (pinfunction "P_1") (pintype "passive"))
      (node (ref "L3") (pin "1") (pinfunction "1_1") (pintype "passive"))
    )
    (net (code "85") (name "Net-(IC5-FB)") (class "Default")
      (node (ref "IC5") (pin "3") (pinfunction "FB_3") (pintype "bidirectional"))
      (node (ref "R35") (pin "1") (pinfunction "1_1") (pintype "passive"))
      (node (ref "R36") (pin "2") (pinfunction "2_2") (pintype "passive"))
    )
    (net (code "86") (name "Net-(IC6-CD+)") (class "Default")
      (node (ref "IC6") (pin "9") (pinfunction "CD+_9") (pintype "passive"))
      (node (ref "JP8") (pin "1") (pinfunction "1_1") (pintype "passive"))
    )
    (net (code "87") (name "Net-(IC7-+INC)") (class "Default")
      (node (ref "C33") (pin "1") (pinfunction "1_1") (pintype "passive"))
      (node (ref "IC7") (pin "11") (pinfunction "+IND_11") (pintype "bidirectional"))
      (node (ref "IC7") (pin "9") (pinfunction "+INC_9") (pintype "bidirectional"))
      (node (ref "R38") (pin "2") (pinfunction "2_2") (pintype "passive"))
    )
    (net (code "88") (name "Net-(IC7--INA)") (class "Default")
      (node (ref "C32") (pin "2") (pinfunction "2_2") (pintype "passive"))
      (node (ref "IC7") (pin "4") (pinfunction "-INA_4") (pintype "bidirectional"))
      (node (ref "IC7") (pin "6") (pinfunction "-INB_6") (pintype "bidirectional"))
      (node (ref "R37") (pin "2") (pinfunction "2_2") (pintype "passive"))
    )
    (net (code "89") (name "Net-(JP7-Pad4)") (class "Default")
      (node (ref "JP7") (pin "4") (pinfunction "4_4") (pintype "passive"))
      (node (ref "R47") (pin "1") (pinfunction "1_1") (pintype "passive"))
    )
    (net (code "90") (name "Net-(JP7-Pad6)") (class "Default")
      (node (ref "JP7") (pin "6") (pinfunction "6_6") (pintype "passive"))
      (node (ref "R48") (pin "1") (pinfunction "1_1") (pintype "passive"))
    )
    (net (code "91") (name "Net-(JP7-Pad9)") (class "Default")
      (node (ref "JP7") (pin "9") (pinfunction "9_9") (pintype "passive"))
      (node (ref "R49") (pin "2") (pinfunction "2_2") (pintype "passive"))
    )
    (net (code "92") (name "Net-(JP7-Pad13)") (class "Default")
      (node (ref "JP7") (pin "13") (pinfunction "13_13") (pintype "passive"))
      (node (ref "R39") (pin "1") (pinfunction "1_1") (pintype "passive"))
    )
    (net (code "93") (name "Net-(JP15-P)") (class "Default")
      (node (ref "C2") (pin "1") (pinfunction "1_1") (pintype "passive"))
      (node (ref "JP1") (pin "1") (pinfunction "1_1") (pintype "passive"))
      (node (ref "JP15") (pin "1") (pinfunction "P_1") (pintype "passive"))
      (node (ref "L1") (pin "2") (pinfunction "2_2") (pintype "passive"))
    )
    (net (code "94") (name "Net-(PWR-PadA)") (class "Default")
      (node (ref "PWR") (pin "A") (pinfunction "A_A") (pintype "passive"))
      (node (ref "R32") (pin "2") (pinfunction "2_2") (pintype "passive"))
    )
    (net (code "95") (name "Net-(R40-Pad2)") (class "Default")
      (node (ref "R40") (pin "2") (pinfunction "2_2") (pintype "passive"))
      (node (ref "R41") (pin "1") (pinfunction "1_1") (pintype "passive"))
    )
    (net (code "96") (name "VCC") (class "Default")
      (node (ref "C19") (pin "1") (pinfunction "1_1") (pintype "passive"))
      (node (ref "C20") (pin "+") (pinfunction "+_+") (pintype "passive"))
      (node (ref "C28") (pin "1") (pinfunction "1_1") (pintype "passive"))
      (node (ref "IC1") (pin "4") (pinfunction "FB_4") (pintype "input"))
      (node (ref "IC3") (pin "3") (pinfunction "VCC_3") (pintype "power_in"))
      (node (ref "IC5") (pin "4") (pinfunction "EN_4") (pintype "bidirectional"))
      (node (ref "IC5") (pin "5") (pinfunction "VIN_5") (pintype "bidirectional"))
      (node (ref "IC7") (pin "3") (pinfunction "VCC_3") (pintype "bidirectional"))
      (node (ref "IC8") (pin "3") (pinfunction "VIN_3") (pintype "input"))
      (node (ref "JP12") (pin "1") (pinfunction "P_1") (pintype "passive"))
      (node (ref "JP3") (pin "1") (pinfunction "1_1") (pintype "passive"))
      (node (ref "JP3") (pin "5") (pinfunction "5_5") (pintype "passive"))
      (node (ref "JP3") (pin "9") (pinfunction "9_9") (pintype "passive"))
      (node (ref "JP7") (pin "1") (pinfunction "1_1") (pintype "passive"))
      (node (ref "JP7") (pin "11") (pinfunction "11_11") (pintype "passive"))
      (node (ref "JP7") (pin "12") (pinfunction "12_12") (pintype "passive"))
      (node (ref "JP7") (pin "2") (pinfunction "2_2") (pintype "passive"))
      (node (ref "JP7") (pin "8") (pinfunction "8_8") (pintype "passive"))
      (node (ref "L2") (pin "1") (pinfunction "1_1") (pintype "passive"))
      (node (ref "L4") (pin "1") (pinfunction "1_1") (pintype "passive"))
      (node (ref "L5") (pin "2") (pinfunction "2_2") (pintype "passive"))
      (node (ref "PAD4") (pin "1") (pinfunction "P_1") (pintype "passive"))
      (node (ref "R11") (pin "2") (pinfunction "2_2") (pintype "passive"))
      (node (ref "R15") (pin "2") (pinfunction "2_2") (pintype "passive"))
      (node (ref "R17") (pin "1") (pinfunction "1_1") (pintype "passive"))
      (node (ref "R18") (pin "1") (pinfunction "1_1") (pintype "passive"))
      (node (ref "R28") (pin "1") (pinfunction "1_1") (pintype "passive"))
      (node (ref "R43") (pin "2") (pinfunction "2_2") (pintype "passive"))
      (node (ref "R45") (pin "2") (pinfunction "2_2") (pintype "passive"))
    )
    (net (code "97") (name "VCCIO") (class "Default")
      (node (ref "C22") (pin "1") (pinfunction "1_1") (pintype "passive"))
      (node (ref "C23") (pin "2") (pinfunction "2_2") (pintype "passive"))
      (node (ref "C25") (pin "2") (pinfunction "2_2") (pintype "passive"))
      (node (ref "C29") (pin "2") (pinfunction "2_2") (pintype "passive"))
      (node (ref "C30") (pin "2") (pinfunction "2_2") (pintype "passive"))
      (node (ref "IC3") (pin "5") (pinfunction "SPLIT_5") (pintype "bidirectional"))
      (node (ref "IC4") (pin "1") (pinfunction "VBAT_1") (pintype "input"))
      (node (ref "IC4") (pin "19") (pinfunction "VDD_4_19") (pintype "power_in"))
      (node (ref "IC4") (pin "32") (pinfunction "VDD_1_32") (pintype "power_in"))
      (node (ref "IC4") (pin "48") (pinfunction "VDD_2_48") (pintype "power_in"))
      (node (ref "IC4") (pin "64") (pinfunction "VDD_3_64") (pintype "power_in"))
      (node (ref "IC8") (pin "2") (pinfunction "VOUT_2") (pintype "output"))
      (node (ref "IC9A") (pin "5") (pinfunction "VCC_5") (pintype "bidirectional"))
      (node (ref "IC9B") (pin "14") (pinfunction "VCC_14") (pintype "power_in"))
      (node (ref "JP10") (pin "1") (pinfunction "P_1") (pintype "passive"))
      (node (ref "JP14") (pin "1") (pinfunction "P_1") (pintype "passive"))
      (node (ref "JP6") (pin "1") (pinfunction "1_1") (pintype "passive"))
      (node (ref "L1") (pin "1") (pinfunction "1_1") (pintype "passive"))
      (node (ref "L3") (pin "2") (pinfunction "2_2") (pintype "passive"))
      (node (ref "R32") (pin "1") (pinfunction "1_1") (pintype "passive"))
      (node (ref "R33") (pin "1") (pinfunction "1_1") (pintype "passive"))
      (node (ref "R34") (pin "2") (pinfunction "2_2") (pintype "passive"))
    )
    (net (code "98") (name "unconnected-(IC2A-IN2+-Pad6)") (class "Default")
      (node (ref "IC2A") (pin "6") (pinfunction "IN2+_6") (pintype "input"))
    )
    (net (code "99") (name "unconnected-(IC2A-IN2--Pad5)") (class "Default")
      (node (ref "IC2A") (pin "5") (pinfunction "IN2-_5") (pintype "input"))
    )
    (net (code "100") (name "unconnected-(IC2A-OUT2-Pad3)") (class "Default")
      (node (ref "IC2A") (pin "3") (pinfunction "OUT2_3") (pintype "output"))
    )
    (net (code "101") (name "unconnected-(IC2B-BYPASS-Pad7)") (class "Default")
      (node (ref "IC2B") (pin "7") (pinfunction "BYPASS_7") (pintype "passive"))
    )
    (net (code "102") (name "unconnected-(IC2B-GAIN-Pad1)") (class "Default")
      (node (ref "IC2B") (pin "1") (pinfunction "GAIN_1") (pintype "passive"))
    )
    (net (code "103") (name "unconnected-(IC2B-GAIN-Pad8)") (class "Default")
      (node (ref "IC2B") (pin "8") (pinfunction "GAIN_8") (pintype "passive"))
    )
    (net (code "104") (name "unconnected-(IC4-PA0-WKUP-Pad14)") (class "Default")
      (node (ref "IC4") (pin "14") (pinfunction "PA0-WKUP_14") (pintype "bidirectional"))
    )
    (net (code "105") (name "unconnected-(IC4-PA15-Pad50)") (class "Default")
      (node (ref "IC4") (pin "50") (pinfunction "PA15_50") (pintype "bidirectional"))
    )
    (net (code "106") (name "unconnected-(IC4-PB2-Pad28)") (class "Default")
      (node (ref "IC4") (pin "28") (pinfunction "PB2_28") (pintype "bidirectional"))
    )
    (net (code "107") (name "unconnected-(IC4-PB3-Pad55)") (class "Default")
      (node (ref "IC4") (pin "55") (pinfunction "PB3_55") (pintype "bidirectional"))
    )
    (net (code "108") (name "unconnected-(IC4-PB4-Pad56)") (class "Default")
      (node (ref "IC4") (pin "56") (pinfunction "PB4_56") (pintype "bidirectional"))
    )
    (net (code "109") (name "unconnected-(IC4-PC14-OSC32_IN-Pad3)") (class "Default")
      (node (ref "IC4") (pin "3") (pinfunction "PC14-OSC32_IN_3") (pintype "bidirectional"))
    )
    (net (code "110") (name "unconnected-(IC4-PC15-OSC32_OUT-Pad4)") (class "Default")
      (node (ref "IC4") (pin "4") (pinfunction "PC15-OSC32_OUT_4") (pintype "bidirectional"))
    )
    (net (code "111") (name "unconnected-(IC9B-2A-Pad3)") (class "Default")
      (node (ref "IC9B") (pin "3") (pinfunction "2A_3") (pintype "bidirectional"))
    )
    (net (code "112") (name "unconnected-(IC9B-2B-Pad4)") (class "Default")
      (node (ref "IC9B") (pin "4") (pinfunction "2B_4") (pintype "bidirectional"))
    )
    (net (code "113") (name "unconnected-(IC9B-2C-Pad5)") (class "Default")
      (node (ref "IC9B") (pin "5") (pinfunction "2C_5") (pintype "bidirectional"))
    )
    (net (code "114") (name "unconnected-(IC9B-2Y-Pad6)") (class "Default")
      (node (ref "IC9B") (pin "6") (pinfunction "2Y_6") (pintype "bidirectional"))
    )
    (net (code "115") (name "unconnected-(IC9B-3A-Pad9)") (class "Default")
      (node (ref "IC9B") (pin "9") (pinfunction "3A_9") (pintype "bidirectional"))
    )
    (net (code "116") (name "unconnected-(IC9B-3B-Pad10)") (class "Default")
      (node (ref "IC9B") (pin "10") (pinfunction "3B_10") (pintype "bidirectional"))
    )
    (net (code "117") (name "unconnected-(IC9B-3C-Pad11)") (class "Default")
      (node (ref "IC9B") (pin "11") (pinfunction "3C_11") (pintype "bidirectional"))
    )
    (net (code "118") (name "unconnected-(IC9B-3Y-Pad8)") (class "Default")
      (node (ref "IC9B") (pin "8") (pinfunction "3Y_8") (pintype "bidirectional"))
    )
    (net (code "119") (name "unconnected-(JP1-Pad5)") (class "Default")
      (node (ref "JP1") (pin "5") (pinfunction "5_5") (pintype "passive"))
    )
    (net (code "120") (name "unconnected-(JP1-Pad6)") (class "Default")
      (node (ref "JP1") (pin "6") (pinfunction "6_6") (pintype "passive"))
    )
    (net (code "121") (name "unconnected-(JP1-Pad7)") (class "Default")
      (node (ref "JP1") (pin "7") (pinfunction "7_7") (pintype "passive"))
    )
    (net (code "122") (name "unconnected-(JP1-Pad8)") (class "Default")
      (node (ref "JP1") (pin "8") (pinfunction "8_8") (pintype "passive"))
    )
    (net (code "123") (name "unconnected-(JP1-Pad9)") (class "Default")
      (node (ref "JP1") (pin "9") (pinfunction "9_9") (pintype "passive"))
    )
    (net (code "124") (name "unconnected-(JP1-Pad10)") (class "Default")
      (node (ref "JP1") (pin "10") (pinfunction "10_10") (pintype "passive"))
    )
    (net (code "125") (name "unconnected-(JP3-Pad14)") (class "Default")
      (node (ref "JP3") (pin "14") (pinfunction "14_14") (pintype "passive"))
    )
    (net (code "126") (name "unconnected-(JP6-Pad6)") (class "Default")
      (node (ref "JP6") (pin "6") (pinfunction "6_6") (pintype "passive"))
    )
    (net (code "127") (name "unconnected-(JP6-Pad7)") (class "Default")
      (node (ref "JP6") (pin "7") (pinfunction "7_7") (pintype "passive"))
    )
    (net (code "128") (name "unconnected-(JP6-Pad8)") (class "Default")
      (node (ref "JP6") (pin "8") (pinfunction "8_8") (pintype "passive"))
    )
    (net (code "129") (name "unconnected-(JP6-Pad9)") (class "Default")
      (node (ref "JP6") (pin "9") (pinfunction "9_9") (pintype "passive"))
    )
    (net (code "130") (name "unconnected-(JP7-Pad3)") (class "Default")
      (node (ref "JP7") (pin "3") (pinfunction "3_3") (pintype "passive"))
    )
    (net (code "131") (name "unconnected-(JP7-Pad14)") (class "Default")
      (node (ref "JP7") (pin "14") (pinfunction "14_14") (pintype "passive"))
    )
    (net (code "132") (name "unconnected-(TP1-PadTP)") (class "Default")
      (node (ref "TP1") (pin "TP") (pinfunction "TP_TP") (pintype "input"))
    )
  )
)
